# design.net
KiCad netlist of a schematic drawn in Altium Designer
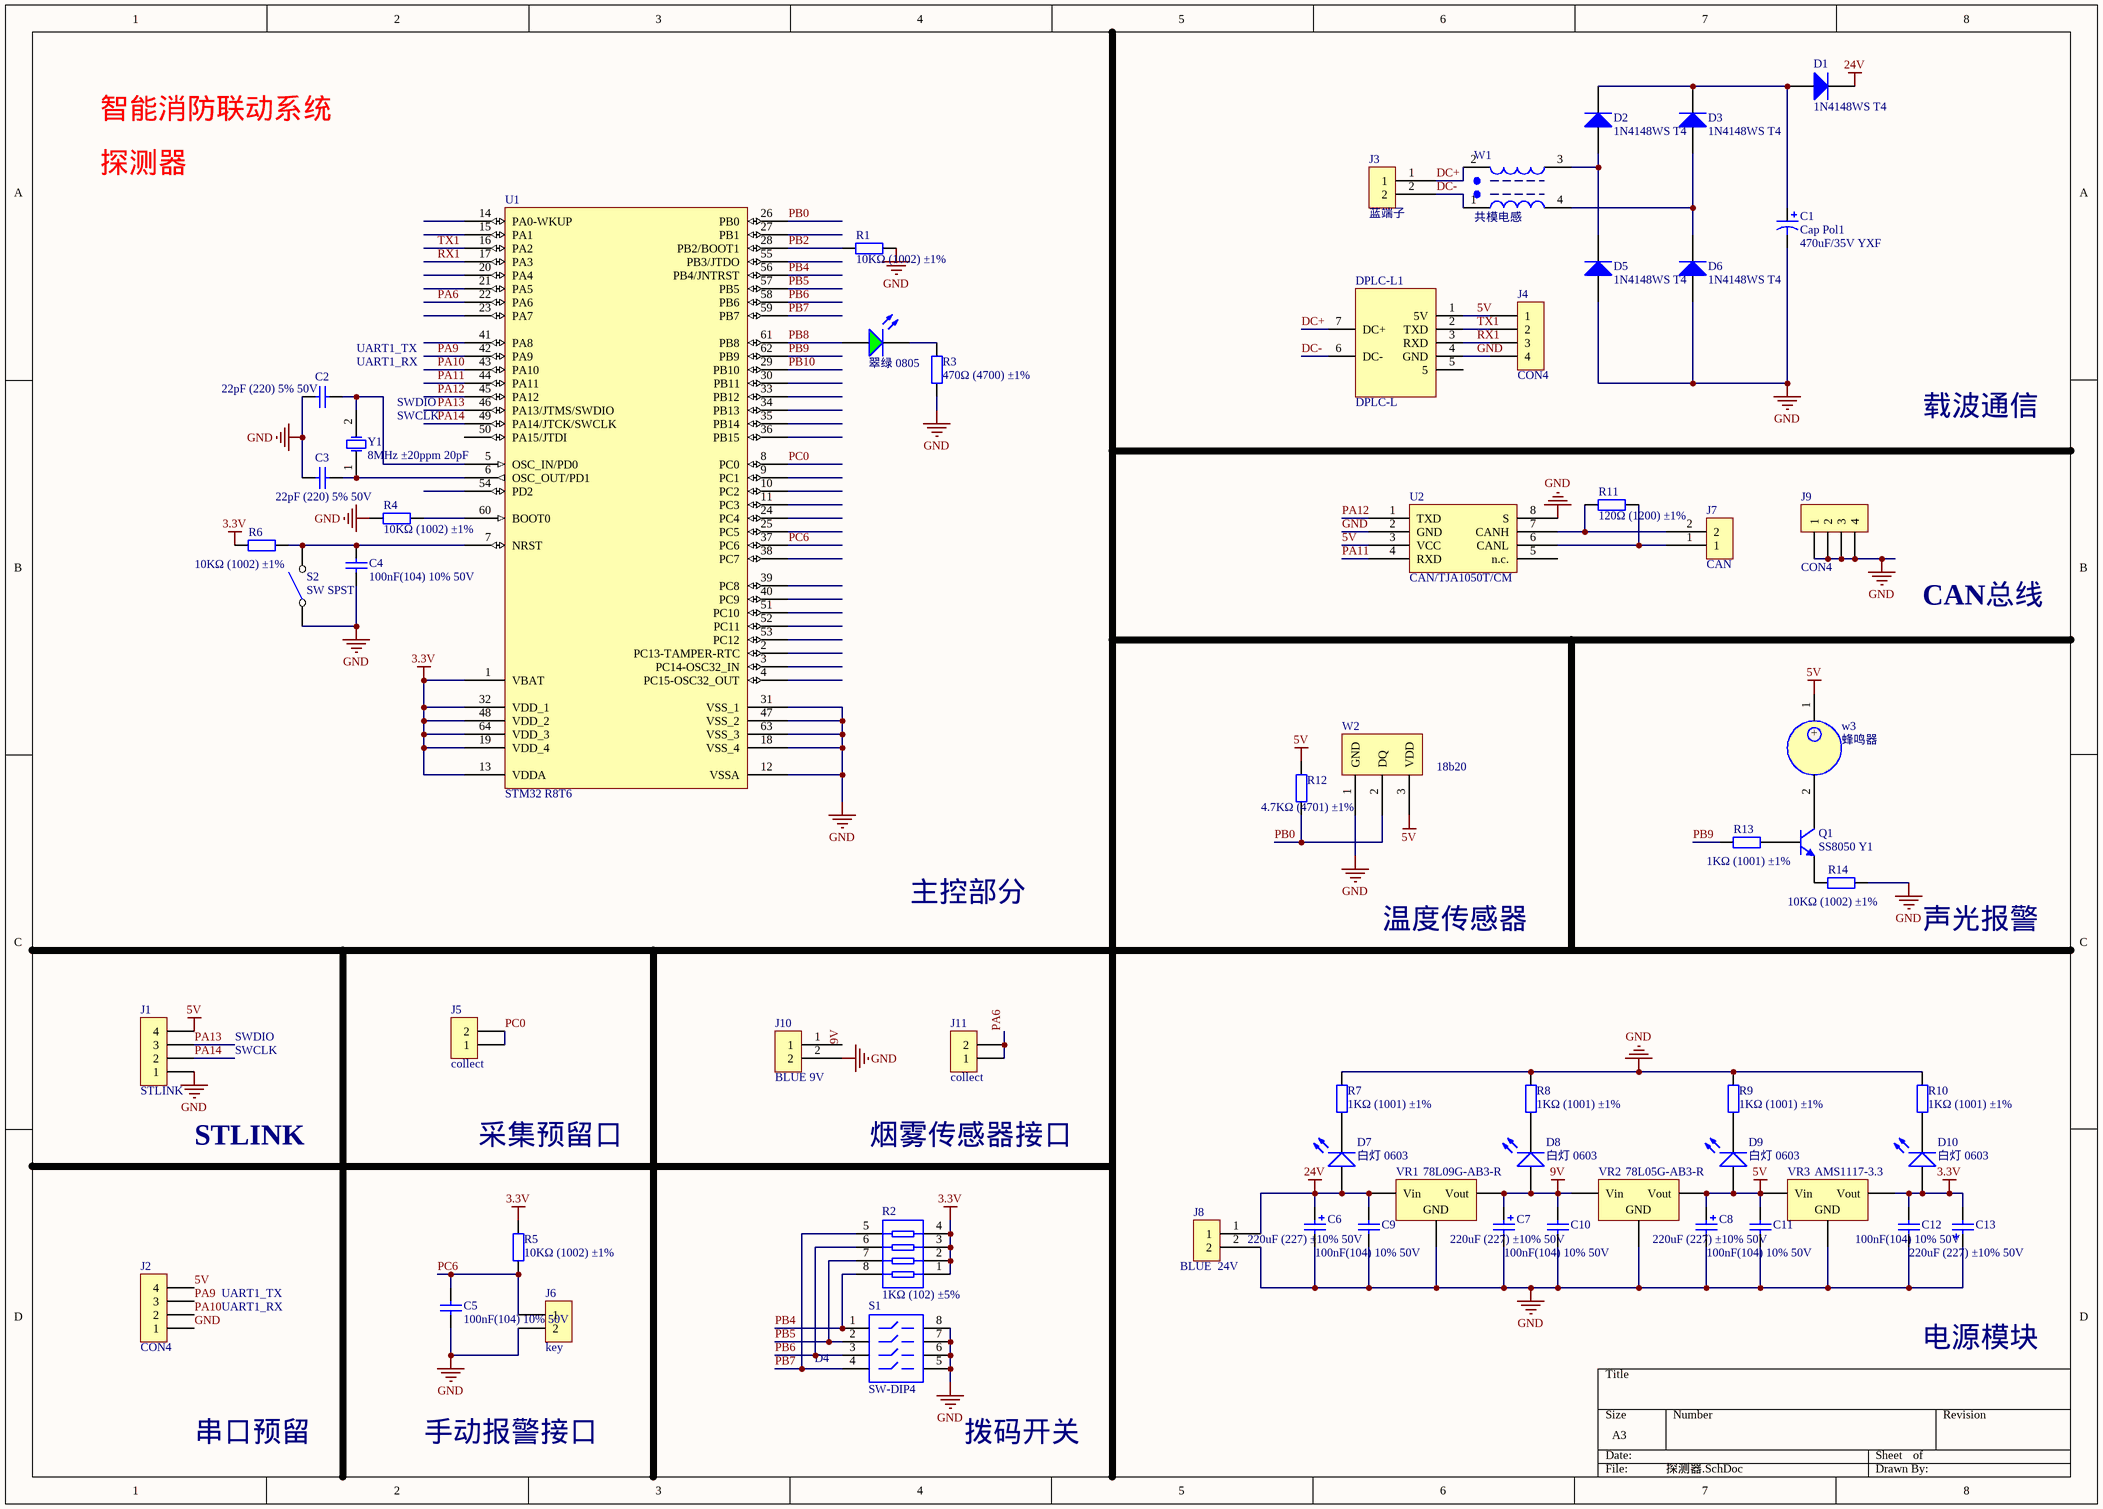
[diagram p0: 探测器.SchDoc]

(export (version "E")
  (design (tool "Eeschema 10.0.6"))
  (components
    (comp (ref "C1")
      (value "Cap Pol1")
      (footprint "RB.2/.4")
      (description "Polarized Capacitor (Radial)")
      (fields (field (name "ALTIUM_VALUE") "470uF/35V YXF") (field (name "PUBLISHER") "Altium Limited"))
      (libsource (lib "Miscellaneous Devices") (part "Cap Pol1"))
    )
    (comp (ref "C2")
      (value "22pF (220) 5% 50V")
      (footprint "LC-0805_C")
      (description "贴片电容")
      (libsource (lib "Miscellaneous Devices LC") (part "0805 22pF (220) 5% 50V"))
    )
    (comp (ref "C3")
      (value "22pF (220) 5% 50V")
      (footprint "LC-0805_C")
      (description "贴片电容")
      (libsource (lib "Miscellaneous Devices LC") (part "0805 22pF (220) 5% 50V"))
    )
    (comp (ref "C4")
      (value "100nF(104) 10% 50V")
      (footprint "LC-0805_C")
      (description "贴片电容")
      (libsource (lib "Miscellaneous Devices LC") (part "0805 100nF(104) 10% 50V"))
    )
    (comp (ref "C5")
      (value "100nF(104) 10% 50V")
      (footprint "LC-0805_C")
      (description "贴片电容")
      (libsource (lib "Miscellaneous Devices LC") (part "0805 100nF(104) 10% 50V"))
    )
    (comp (ref "C6")
      (value "220uF (227) ±10% 50V")
      (footprint "LC-CASE-B_3528")
      (description "钽电容")
      (libsource (lib "Miscellaneous Devices LC") (part "3528 100uF (107) 10% 6.3V"))
    )
    (comp (ref "C7")
      (value "220uF (227) ±10% 50V")
      (footprint "LC-CASE-B_3528")
      (description "钽电容")
      (libsource (lib "Miscellaneous Devices LC") (part "3528 100uF (107) 10% 6.3V"))
    )
    (comp (ref "C8")
      (value "220uF (227) ±10% 50V")
      (footprint "LC-CASE-B_3528")
      (description "钽电容")
      (libsource (lib "Miscellaneous Devices LC") (part "3528 100uF (107) 10% 6.3V"))
    )
    (comp (ref "C9")
      (value "100nF(104) 10% 50V")
      (footprint "LC-0805_C")
      (description "贴片电容")
      (libsource (lib "Miscellaneous Devices LC") (part "0805 100nF(104) 10% 50V"))
    )
    (comp (ref "C10")
      (value "100nF(104) 10% 50V")
      (footprint "LC-0805_C")
      (description "贴片电容")
      (libsource (lib "Miscellaneous Devices LC") (part "0805 100nF(104) 10% 50V"))
    )
    (comp (ref "C11")
      (value "100nF(104) 10% 50V")
      (footprint "LC-0805_C")
      (description "贴片电容")
      (libsource (lib "Miscellaneous Devices LC") (part "0805 100nF(104) 10% 50V"))
    )
    (comp (ref "C12")
      (value "100nF(104) 10% 50V")
      (footprint "LC-0805_C")
      (description "贴片电容")
      (libsource (lib "Miscellaneous Devices LC") (part "0805 100nF(104) 10% 50V"))
    )
    (comp (ref "C13")
      (value "220uF (227) ±10% 50V")
      (footprint "LC-CASE-B_3528")
      (description "钽电容")
      (libsource (lib "Miscellaneous Devices LC") (part "3528 100uF (107) 10% 6.3V"))
    )
    (comp (ref "D1")
      (value "1N4148WS T4")
      (footprint "LC-SOD-323")
      (description "二极管")
      (libsource (lib "Miscellaneous Devices LC") (part "SOD-323 1N4148WS T4"))
    )
    (comp (ref "D2")
      (value "1N4148WS T4")
      (footprint "LC-SOD-323")
      (description "二极管")
      (libsource (lib "Miscellaneous Devices LC") (part "SOD-323 1N4148WS T4"))
    )
    (comp (ref "D3")
      (value "1N4148WS T4")
      (footprint "LC-SOD-323")
      (description "二极管")
      (libsource (lib "Miscellaneous Devices LC") (part "SOD-323 1N4148WS T4"))
    )
    (comp (ref "D4")
      (value "翠绿 0805")
      (footprint "LC-0805_LED_S1")
      (description "发光二极管")
      (libsource (lib "Miscellaneous Devices LC") (part "0805 翠绿"))
    )
    (comp (ref "D5")
      (value "1N4148WS T4")
      (footprint "LC-SOD-323")
      (description "二极管")
      (libsource (lib "Miscellaneous Devices LC") (part "SOD-323 1N4148WS T4"))
    )
    (comp (ref "D6")
      (value "1N4148WS T4")
      (footprint "LC-SOD-323")
      (description "二极管")
      (libsource (lib "Miscellaneous Devices LC") (part "SOD-323 1N4148WS T4"))
    )
    (comp (ref "D7")
      (value "白灯 0603")
      (footprint "LC-0603_LED_S1")
      (description "发光二极管")
      (libsource (lib "Miscellaneous Devices LC") (part "0603 白灯"))
    )
    (comp (ref "D8")
      (value "白灯 0603")
      (footprint "LC-0603_LED_S1")
      (description "发光二极管")
      (libsource (lib "Miscellaneous Devices LC") (part "0603 白灯"))
    )
    (comp (ref "D9")
      (value "白灯 0603")
      (footprint "LC-0603_LED_S1")
      (description "发光二极管")
      (libsource (lib "Miscellaneous Devices LC") (part "0603 白灯"))
    )
    (comp (ref "D10")
      (value "白灯 0603")
      (footprint "LC-0603_LED_S1")
      (description "发光二极管")
      (libsource (lib "Miscellaneous Devices LC") (part "0603 白灯"))
    )
    (comp (ref "DPLC-L1") (value "DPLC-L") (footprint "DPLC-L") (libsource (lib "毕设原理图封装库") (part "DPLC-L")))
    (comp (ref "J1") (value "STLINK") (footprint "SIP4") (libsource (lib "") (part "CON4_1")))
    (comp (ref "J2") (value "CON4") (footprint "SIP4") (libsource (lib "") (part "CON4_1")))
    (comp (ref "J3") (value "蓝端子") (footprint "蓝端子") (libsource (lib "毕设原理图封装库") (part "蓝端子")))
    (comp (ref "J4") (value "CON4") (footprint "SIP4") (libsource (lib "") (part "CON4_2")))
    (comp (ref "J5") (value "collect") (footprint "SIP2") (libsource (lib "") (part "CON2_1")))
    (comp (ref "J6") (value "key") (footprint "SIP2") (libsource (lib "毕设原理图封装库") (part "CON2")))
    (comp (ref "J7") (value "CAN") (footprint "蓝端子") (libsource (lib "") (part "蓝端子_1")))
    (comp (ref "J8") (value "BLUE  24V") (footprint "蓝端子") (libsource (lib "毕设原理图封装库") (part "蓝端子")))
    (comp (ref "J9") (value "CON4") (footprint "SIP4") (libsource (lib "毕设原理图封装库") (part "CON4")))
    (comp (ref "J10") (value "BLUE 9V") (footprint "蓝端子") (libsource (lib "毕设原理图封装库") (part "蓝端子")))
    (comp (ref "J11") (value "collect") (footprint "SIP2") (libsource (lib "") (part "CON2_1")))
    (comp (ref "Q1")
      (value "SS8050 Y1")
      (footprint "LC-SOT-23(SOT-23-3)")
      (description "三极管")
      (libsource (lib "Miscellaneous Devices LC") (part "SOT-23 SS8050 Y1"))
    )
    (comp (ref "R1")
      (value "10KΩ (1002) ±1%")
      (footprint "LC-0805_R")
      (description "贴片电阻")
      (libsource (lib "Miscellaneous Devices LC") (part "0805 10KΩ (1002) 1%"))
    )
    (comp (ref "R2")
      (value "1KΩ (102) ±5%")
      (footprint "LC-0603_Rx4")
      (description "贴片排阻")
      (libsource (lib "Miscellaneous Devices LC") (part "0603*4  1KΩ (102) 5%"))
    )
    (comp (ref "R3")
      (value "470Ω (4700) ±1%")
      (footprint "LC-0805_R")
      (description "贴片电阻")
      (libsource (lib "Miscellaneous Devices LC") (part "0805 470Ω (4700) 1%"))
    )
    (comp (ref "R4")
      (value "10KΩ (1002) ±1%")
      (footprint "LC-0805_R")
      (description "贴片电阻")
      (libsource (lib "") (part "0805 10KΩ (1002) 1%_1"))
    )
    (comp (ref "R5")
      (value "10KΩ (1002) ±1%")
      (footprint "LC-0805_R")
      (description "贴片电阻")
      (libsource (lib "") (part "0805 10KΩ (1002) 1%_2"))
    )
    (comp (ref "R6")
      (value "10KΩ (1002) ±1%")
      (footprint "LC-0805_R")
      (description "贴片电阻")
      (libsource (lib "") (part "0805 10KΩ (1002) 1%_1"))
    )
    (comp (ref "R7")
      (value "1KΩ (1001) ±1%")
      (footprint "LC-0603_R")
      (description "贴片电阻")
      (libsource (lib "Miscellaneous Devices LC") (part "0603 1KΩ (1001) 1%"))
    )
    (comp (ref "R8")
      (value "1KΩ (1001) ±1%")
      (footprint "LC-0603_R")
      (description "贴片电阻")
      (libsource (lib "Miscellaneous Devices LC") (part "0603 1KΩ (1001) 1%"))
    )
    (comp (ref "R9")
      (value "1KΩ (1001) ±1%")
      (footprint "LC-0603_R")
      (description "贴片电阻")
      (libsource (lib "Miscellaneous Devices LC") (part "0603 1KΩ (1001) 1%"))
    )
    (comp (ref "R10")
      (value "1KΩ (1001) ±1%")
      (footprint "LC-0603_R")
      (description "贴片电阻")
      (libsource (lib "Miscellaneous Devices LC") (part "0603 1KΩ (1001) 1%"))
    )
    (comp (ref "R11")
      (value "120Ω (1200) ±1%")
      (footprint "LC-0805_R")
      (description "贴片电阻")
      (libsource (lib "Miscellaneous Devices LC") (part "0805 120Ω (1200) 1%"))
    )
    (comp (ref "R12")
      (value "4.7KΩ (4701) ±1%")
      (footprint "LC-0805_R")
      (description "贴片电阻")
      (libsource (lib "Miscellaneous Devices LC") (part "0805 4.7KΩ (4701) 1%"))
    )
    (comp (ref "R13")
      (value "1KΩ (1001) ±1%")
      (footprint "LC-0805_R")
      (description "贴片电阻")
      (libsource (lib "Miscellaneous Devices LC") (part "0805 1KΩ (1001) 1%"))
    )
    (comp (ref "R14")
      (value "10KΩ (1002) ±1%")
      (footprint "LC-0805_R")
      (description "贴片电阻")
      (libsource (lib "") (part "0805 10KΩ (1002) 1%_1"))
    )
    (comp (ref "S1")
      (value "SW-DIP4")
      (footprint "4位拨码开关")
      (description "4位拨码开关")
      (libsource (lib "毕设原理图封装库") (part "SW-DIP4"))
    )
    (comp (ref "S2")
      (value "SW SPST")
      (footprint "单片机小按键")
      (description "单刀单掷开关")
      (libsource (lib "毕设原理图封装库") (part "SW SPST"))
    )
    (comp (ref "U1")
      (value "STM32 R8T6")
      (footprint "LC-LQFP-64_10x10x05P")
      (libsource (lib "毕设原理图封装库") (part "STM32 R8T6"))
    )
    (comp (ref "U2")
      (value "CAN/TJA1050T/CM")
      (footprint "LC-SOIC-8_150mil")
      (description "CAN")
      (libsource (lib "Miscellaneous Devices LC") (part "CAN/TJA1050T/CM"))
    )
    (comp (ref "VR1")
      (value "78L09G-AB3-R")
      (footprint "LC-SOT-89(SOT-89-3)")
      (description "低压差线性稳压(LDO)")
      (libsource (lib "Miscellaneous Devices LC") (part "SOT-89 78L12G-AB3-R"))
    )
    (comp (ref "VR2")
      (value "78L05G-AB3-R")
      (footprint "LC-SOT-89(SOT-89-3)")
      (description "低压差线性稳压(LDO)")
      (libsource (lib "Miscellaneous Devices LC") (part "SOT-89 78L05G-AB3-R"))
    )
    (comp (ref "VR3")
      (value "AMS1117-3.3")
      (footprint "LC-SOT-223")
      (description "低压差线性稳压(LDO)")
      (libsource (lib "Miscellaneous Devices LC") (part "SOT-223 AMS1117-3.3"))
    )
    (comp (ref "W1") (value "共模电感") (footprint "共模电感") (libsource (lib "毕设原理图封装库") (part "共模电感")))
    (comp (ref "W2") (value "18b20") (footprint "DS18B20") (libsource (lib "毕设原理图封装库") (part "18b20")))
    (comp (ref "w3") (value "蜂鸣器") (footprint "蜂鸣器") (libsource (lib "毕设原理图封装库") (part "蜂鸣器")))
    (comp (ref "Y1")
      (value "8MHz ±20ppm 20pF")
      (footprint "LC-SMD-5032_2P")
      (description "贴片晶振")
      (libsource (lib "Miscellaneous Devices LC") (part "SMD-5032_2P 8MHz 20ppm 20pF"))
    )
  )
  (nets
    (net (code "1") (name "/DC+") (class "Default")
      (node (ref "DPLC-L1") (pin "7") (pinfunction "DC+_7") (pintype "passive"))
      (node (ref "J3") (pin "1") (pinfunction "1_1") (pintype "passive"))
      (node (ref "W1") (pin "2") (pinfunction "2_2") (pintype "passive"))
    )
    (net (code "2") (name "/DC-") (class "Default")
      (node (ref "DPLC-L1") (pin "6") (pinfunction "DC-_6") (pintype "passive"))
      (node (ref "J3") (pin "2") (pinfunction "2_2") (pintype "passive"))
      (node (ref "W1") (pin "1") (pinfunction "1_1") (pintype "passive"))
    )
    (net (code "3") (name "/PA6") (class "Default")
      (node (ref "J11") (pin "1") (pinfunction "1_1") (pintype "passive"))
      (node (ref "J11") (pin "2") (pinfunction "2_2") (pintype "passive"))
      (node (ref "U1") (pin "22") (pinfunction "PA6_22") (pintype "bidirectional"))
    )
    (net (code "4") (name "/PA9") (class "Default")
      (node (ref "J2") (pin "3") (pinfunction "3_3") (pintype "passive"))
      (node (ref "U1") (pin "42") (pinfunction "PA9_42") (pintype "bidirectional"))
    )
    (net (code "5") (name "/PA10") (class "Default")
      (node (ref "J2") (pin "2") (pinfunction "2_2") (pintype "passive"))
      (node (ref "U1") (pin "43") (pinfunction "PA10_43") (pintype "bidirectional"))
    )
    (net (code "6") (name "/PA11") (class "Default")
      (node (ref "U1") (pin "44") (pinfunction "PA11_44") (pintype "bidirectional"))
      (node (ref "U2") (pin "4") (pinfunction "RXD_4") (pintype "passive"))
    )
    (net (code "7") (name "/PA12") (class "Default")
      (node (ref "U1") (pin "45") (pinfunction "PA12_45") (pintype "bidirectional"))
      (node (ref "U2") (pin "1") (pinfunction "TXD_1") (pintype "passive"))
    )
    (net (code "8") (name "/PA13") (class "Default")
      (node (ref "J1") (pin "3") (pinfunction "3_3") (pintype "passive"))
      (node (ref "U1") (pin "46") (pinfunction "PA13/JTMS/SWDIO_46") (pintype "bidirectional"))
    )
    (net (code "9") (name "/PA14") (class "Default")
      (node (ref "J1") (pin "2") (pinfunction "2_2") (pintype "passive"))
      (node (ref "U1") (pin "49") (pinfunction "PA14/JTCK/SWCLK_49") (pintype "bidirectional"))
    )
    (net (code "10") (name "/PB0") (class "Default")
      (node (ref "R12") (pin "1") (pinfunction "1_1") (pintype "passive"))
      (node (ref "U1") (pin "26") (pinfunction "PB0_26") (pintype "bidirectional"))
      (node (ref "W2") (pin "2") (pinfunction "DQ_2") (pintype "passive"))
    )
    (net (code "11") (name "/PB2") (class "Default")
      (node (ref "R1") (pin "2") (pinfunction "2_2") (pintype "passive"))
      (node (ref "U1") (pin "28") (pinfunction "PB2/BOOT1_28") (pintype "bidirectional"))
    )
    (net (code "12") (name "/PB4") (class "Default")
      (node (ref "R2") (pin "8") (pinfunction "8_8") (pintype "passive"))
      (node (ref "S1") (pin "1") (pinfunction "1_1") (pintype "passive"))
      (node (ref "U1") (pin "56") (pinfunction "PB4/JNTRST_56") (pintype "bidirectional"))
    )
    (net (code "13") (name "/PB5") (class "Default")
      (node (ref "R2") (pin "7") (pinfunction "7_7") (pintype "passive"))
      (node (ref "S1") (pin "2") (pinfunction "2_2") (pintype "passive"))
      (node (ref "U1") (pin "57") (pinfunction "PB5_57") (pintype "bidirectional"))
    )
    (net (code "14") (name "/PB6") (class "Default")
      (node (ref "R2") (pin "6") (pinfunction "6_6") (pintype "passive"))
      (node (ref "S1") (pin "3") (pinfunction "3_3") (pintype "passive"))
      (node (ref "U1") (pin "58") (pinfunction "PB6_58") (pintype "bidirectional"))
    )
    (net (code "15") (name "/PB7") (class "Default")
      (node (ref "R2") (pin "5") (pinfunction "5_5") (pintype "passive"))
      (node (ref "S1") (pin "4") (pinfunction "4_4") (pintype "passive"))
      (node (ref "U1") (pin "59") (pinfunction "PB7_59") (pintype "bidirectional"))
    )
    (net (code "16") (name "/PB8") (class "Default")
      (node (ref "D4") (pin "A") (pinfunction "A_A") (pintype "passive"))
      (node (ref "U1") (pin "61") (pinfunction "PB8_61") (pintype "bidirectional"))
    )
    (net (code "17") (name "/PB9") (class "Default")
      (node (ref "R13") (pin "1") (pinfunction "1_1") (pintype "passive"))
      (node (ref "U1") (pin "62") (pinfunction "PB9_62") (pintype "bidirectional"))
    )
    (net (code "18") (name "/PB10") (class "Default")
      (node (ref "U1") (pin "29") (pinfunction "PB10_29") (pintype "bidirectional"))
    )
    (net (code "19") (name "/PC0") (class "Default")
      (node (ref "J5") (pin "1") (pinfunction "1_1") (pintype "passive"))
      (node (ref "J5") (pin "2") (pinfunction "2_2") (pintype "passive"))
      (node (ref "U1") (pin "8") (pinfunction "PC0_8") (pintype "bidirectional"))
    )
    (net (code "20") (name "/PC6") (class "Default")
      (node (ref "C5") (pin "2") (pinfunction "2_2") (pintype "passive"))
      (node (ref "J6") (pin "1") (pinfunction "1_1") (pintype "passive"))
      (node (ref "R5") (pin "1") (pinfunction "1_1") (pintype "passive"))
      (node (ref "U1") (pin "37") (pinfunction "PC6_37") (pintype "bidirectional"))
    )
    (net (code "21") (name "/RX1") (class "Default")
      (node (ref "DPLC-L1") (pin "3") (pinfunction "RXD_3") (pintype "passive"))
      (node (ref "J4") (pin "3") (pinfunction "3_3") (pintype "passive"))
      (node (ref "U1") (pin "17") (pinfunction "PA3_17") (pintype "bidirectional"))
    )
    (net (code "22") (name "/TX1") (class "Default")
      (node (ref "DPLC-L1") (pin "2") (pinfunction "TXD_2") (pintype "passive"))
      (node (ref "J4") (pin "2") (pinfunction "2_2") (pintype "passive"))
      (node (ref "U1") (pin "16") (pinfunction "PA2_16") (pintype "bidirectional"))
    )
    (net (code "23") (name "3.3V") (class "Default")
      (node (ref "C12") (pin "1") (pinfunction "1_1") (pintype "passive"))
      (node (ref "C13") (pin "2") (pinfunction "2_2") (pintype "passive"))
      (node (ref "D10") (pin "A") (pinfunction "A_A") (pintype "passive"))
      (node (ref "R2") (pin "1") (pinfunction "1_1") (pintype "passive"))
      (node (ref "R2") (pin "2") (pinfunction "2_2") (pintype "passive"))
      (node (ref "R2") (pin "3") (pinfunction "3_3") (pintype "passive"))
      (node (ref "R2") (pin "4") (pinfunction "4_4") (pintype "passive"))
      (node (ref "R5") (pin "2") (pinfunction "2_2") (pintype "passive"))
      (node (ref "R6") (pin "1") (pinfunction "1_1") (pintype "passive"))
      (node (ref "U1") (pin "1") (pinfunction "VBAT_1") (pintype "power_in"))
      (node (ref "U1") (pin "13") (pinfunction "VDDA_13") (pintype "power_in"))
      (node (ref "U1") (pin "19") (pinfunction "VDD_4_19") (pintype "power_in"))
      (node (ref "U1") (pin "32") (pinfunction "VDD_1_32") (pintype "power_in"))
      (node (ref "U1") (pin "48") (pinfunction "VDD_2_48") (pintype "power_in"))
      (node (ref "U1") (pin "64") (pinfunction "VDD_3_64") (pintype "power_in"))
      (node (ref "VR3") (pin "2") (pinfunction "Vout_2") (pintype "passive"))
    )
    (net (code "24") (name "5V") (class "Default")
      (node (ref "C11") (pin "2") (pinfunction "2_2") (pintype "passive"))
      (node (ref "C8") (pin "1") (pinfunction "1_1") (pintype "passive"))
      (node (ref "D9") (pin "A") (pinfunction "A_A") (pintype "passive"))
      (node (ref "DPLC-L1") (pin "1") (pinfunction "5V_1") (pintype "passive"))
      (node (ref "J1") (pin "4") (pinfunction "4_4") (pintype "passive"))
      (node (ref "J2") (pin "4") (pinfunction "4_4") (pintype "passive"))
      (node (ref "J4") (pin "1") (pinfunction "1_1") (pintype "passive"))
      (node (ref "R12") (pin "2") (pinfunction "2_2") (pintype "passive"))
      (node (ref "U2") (pin "3") (pinfunction "VCC_3") (pintype "passive"))
      (node (ref "VR2") (pin "3") (pinfunction "Vout_3") (pintype "passive"))
      (node (ref "VR3") (pin "3") (pinfunction "Vin_3") (pintype "passive"))
      (node (ref "W2") (pin "3") (pinfunction "VDD_3") (pintype "passive"))
      (node (ref "w3") (pin "1") (pinfunction "+_1") (pintype "passive"))
    )
    (net (code "25") (name "9V") (class "Default")
      (node (ref "C10") (pin "2") (pinfunction "2_2") (pintype "passive"))
      (node (ref "C7") (pin "1") (pinfunction "1_1") (pintype "passive"))
      (node (ref "D8") (pin "A") (pinfunction "A_A") (pintype "passive"))
      (node (ref "J10") (pin "1") (pinfunction "1_1") (pintype "passive"))
      (node (ref "VR1") (pin "3") (pinfunction "Vout_3") (pintype "passive"))
      (node (ref "VR2") (pin "1") (pinfunction "Vin_1") (pintype "passive"))
    )
    (net (code "26") (name "24V") (class "Default")
      (node (ref "C6") (pin "1") (pinfunction "1_1") (pintype "passive"))
      (node (ref "C9") (pin "2") (pinfunction "2_2") (pintype "passive"))
      (node (ref "D1") (pin "2") (pinfunction "K_2") (pintype "passive"))
      (node (ref "D7") (pin "A") (pinfunction "A_A") (pintype "passive"))
      (node (ref "J8") (pin "1") (pinfunction "1_1") (pintype "passive"))
      (node (ref "VR1") (pin "1") (pinfunction "Vin_1") (pintype "passive"))
    )
    (net (code "27") (name "GND") (class "Default")
      (node (ref "C1") (pin "2") (pinfunction "2_2") (pintype "passive"))
      (node (ref "C10") (pin "1") (pinfunction "1_1") (pintype "passive"))
      (node (ref "C11") (pin "1") (pinfunction "1_1") (pintype "passive"))
      (node (ref "C12") (pin "2") (pinfunction "2_2") (pintype "passive"))
      (node (ref "C13") (pin "1") (pinfunction "1_1") (pintype "passive"))
      (node (ref "C2") (pin "1") (pinfunction "1_1") (pintype "passive"))
      (node (ref "C3") (pin "1") (pinfunction "1_1") (pintype "passive"))
      (node (ref "C4") (pin "1") (pinfunction "1_1") (pintype "passive"))
      (node (ref "C5") (pin "1") (pinfunction "1_1") (pintype "passive"))
      (node (ref "C6") (pin "2") (pinfunction "2_2") (pintype "passive"))
      (node (ref "C7") (pin "2") (pinfunction "2_2") (pintype "passive"))
      (node (ref "C8") (pin "2") (pinfunction "2_2") (pintype "passive"))
      (node (ref "C9") (pin "1") (pinfunction "1_1") (pintype "passive"))
      (node (ref "D5") (pin "1") (pinfunction "A_1") (pintype "passive"))
      (node (ref "D6") (pin "1") (pinfunction "A_1") (pintype "passive"))
      (node (ref "DPLC-L1") (pin "4") (pinfunction "GND_4") (pintype "passive"))
      (node (ref "J1") (pin "1") (pinfunction "1_1") (pintype "passive"))
      (node (ref "J10") (pin "2") (pinfunction "2_2") (pintype "passive"))
      (node (ref "J2") (pin "1") (pinfunction "1_1") (pintype "passive"))
      (node (ref "J4") (pin "4") (pinfunction "4_4") (pintype "passive"))
      (node (ref "J6") (pin "2") (pinfunction "2_2") (pintype "passive"))
      (node (ref "J8") (pin "2") (pinfunction "2_2") (pintype "passive"))
      (node (ref "J9") (pin "1") (pinfunction "1_1") (pintype "passive"))
      (node (ref "J9") (pin "2") (pinfunction "2_2") (pintype "passive"))
      (node (ref "J9") (pin "3") (pinfunction "3_3") (pintype "passive"))
      (node (ref "J9") (pin "4") (pinfunction "4_4") (pintype "passive"))
      (node (ref "R1") (pin "1") (pinfunction "1_1") (pintype "passive"))
      (node (ref "R10") (pin "1") (pinfunction "1_1") (pintype "passive"))
      (node (ref "R14") (pin "2") (pinfunction "2_2") (pintype "passive"))
      (node (ref "R3") (pin "1") (pinfunction "1_1") (pintype "passive"))
      (node (ref "R4") (pin "1") (pinfunction "1_1") (pintype "passive"))
      (node (ref "R7") (pin "1") (pinfunction "1_1") (pintype "passive"))
      (node (ref "R8") (pin "1") (pinfunction "1_1") (pintype "passive"))
      (node (ref "R9") (pin "1") (pinfunction "1_1") (pintype "passive"))
      (node (ref "S1") (pin "5") (pinfunction "5_5") (pintype "passive"))
      (node (ref "S1") (pin "6") (pinfunction "6_6") (pintype "passive"))
      (node (ref "S1") (pin "7") (pinfunction "7_7") (pintype "passive"))
      (node (ref "S1") (pin "8") (pinfunction "8_8") (pintype "passive"))
      (node (ref "S2") (pin "1") (pinfunction "COMMON_1") (pintype "passive"))
      (node (ref "U1") (pin "12") (pinfunction "VSSA_12") (pintype "power_in"))
      (node (ref "U1") (pin "18") (pinfunction "VSS_4_18") (pintype "power_in"))
      (node (ref "U1") (pin "31") (pinfunction "VSS_1_31") (pintype "power_in"))
      (node (ref "U1") (pin "47") (pinfunction "VSS_2_47") (pintype "power_in"))
      (node (ref "U1") (pin "63") (pinfunction "VSS_3_63") (pintype "power_in"))
      (node (ref "U2") (pin "2") (pinfunction "GND_2") (pintype "passive"))
      (node (ref "U2") (pin "8") (pinfunction "S_8") (pintype "passive"))
      (node (ref "VR1") (pin "2") (pinfunction "GND_2") (pintype "passive"))
      (node (ref "VR2") (pin "2") (pinfunction "GND_2") (pintype "passive"))
      (node (ref "VR3") (pin "1") (pinfunction "GND_1") (pintype "passive"))
      (node (ref "W2") (pin "1") (pinfunction "GND_1") (pintype "passive"))
    )
    (net (code "28") (name "Net-(D1-A)") (class "Default")
      (node (ref "C1") (pin "1") (pinfunction "1_1") (pintype "passive"))
      (node (ref "D1") (pin "1") (pinfunction "A_1") (pintype "passive"))
      (node (ref "D2") (pin "2") (pinfunction "K_2") (pintype "passive"))
      (node (ref "D3") (pin "2") (pinfunction "K_2") (pintype "passive"))
    )
    (net (code "29") (name "Net-(D2-A)") (class "Default")
      (node (ref "D2") (pin "1") (pinfunction "A_1") (pintype "passive"))
      (node (ref "D5") (pin "2") (pinfunction "K_2") (pintype "passive"))
      (node (ref "W1") (pin "3") (pinfunction "3_3") (pintype "passive"))
    )
    (net (code "30") (name "Net-(D3-A)") (class "Default")
      (node (ref "D3") (pin "1") (pinfunction "A_1") (pintype "passive"))
      (node (ref "D6") (pin "2") (pinfunction "K_2") (pintype "passive"))
      (node (ref "W1") (pin "4") (pinfunction "4_4") (pintype "passive"))
    )
    (net (code "31") (name "Net-(D4-PadK)") (class "Default")
      (node (ref "D4") (pin "K") (pinfunction "K_K") (pintype "passive"))
      (node (ref "R3") (pin "2") (pinfunction "2_2") (pintype "passive"))
    )
    (net (code "32") (name "Net-(D7-PadK)") (class "Default")
      (node (ref "D7") (pin "K") (pinfunction "K_K") (pintype "passive"))
      (node (ref "R7") (pin "2") (pinfunction "2_2") (pintype "passive"))
    )
    (net (code "33") (name "Net-(D8-PadK)") (class "Default")
      (node (ref "D8") (pin "K") (pinfunction "K_K") (pintype "passive"))
      (node (ref "R8") (pin "2") (pinfunction "2_2") (pintype "passive"))
    )
    (net (code "34") (name "Net-(D9-PadK)") (class "Default")
      (node (ref "D9") (pin "K") (pinfunction "K_K") (pintype "passive"))
      (node (ref "R9") (pin "2") (pinfunction "2_2") (pintype "passive"))
    )
    (net (code "35") (name "Net-(D10-PadK)") (class "Default")
      (node (ref "D10") (pin "K") (pinfunction "K_K") (pintype "passive"))
      (node (ref "R10") (pin "2") (pinfunction "2_2") (pintype "passive"))
    )
    (net (code "36") (name "Net-(Q1-B)") (class "Default")
      (node (ref "Q1") (pin "1") (pinfunction "B_1") (pintype "passive"))
      (node (ref "R13") (pin "2") (pinfunction "2_2") (pintype "passive"))
    )
    (net (code "37") (name "Net-(Q1-C)") (class "Default")
      (node (ref "Q1") (pin "3") (pinfunction "C_3") (pintype "passive"))
      (node (ref "w3") (pin "2") (pintype "passive"))
    )
    (net (code "38") (name "Net-(Q1-E)") (class "Default")
      (node (ref "Q1") (pin "2") (pinfunction "E_2") (pintype "passive"))
      (node (ref "R14") (pin "1") (pinfunction "1_1") (pintype "passive"))
    )
    (net (code "39") (name "Net-(S2-NO)") (class "Default")
      (node (ref "C4") (pin "2") (pinfunction "2_2") (pintype "passive"))
      (node (ref "R6") (pin "2") (pinfunction "2_2") (pintype "passive"))
      (node (ref "S2") (pin "2") (pinfunction "NO_2") (pintype "passive"))
      (node (ref "U1") (pin "7") (pinfunction "NRST_7") (pintype "bidirectional"))
    )
    (net (code "40") (name "Net-(U1-BOOT0)") (class "Default")
      (node (ref "R4") (pin "2") (pinfunction "2_2") (pintype "passive"))
      (node (ref "U1") (pin "60") (pinfunction "BOOT0_60") (pintype "input"))
    )
    (net (code "41") (name "Net-(U1-OSC_IN{slash}PD0)") (class "Default")
      (node (ref "C2") (pin "2") (pinfunction "2_2") (pintype "passive"))
      (node (ref "U1") (pin "5") (pinfunction "OSC_IN/PD0_5") (pintype "input"))
      (node (ref "Y1") (pin "2") (pinfunction "OSC2_2") (pintype "passive"))
    )
    (net (code "42") (name "Net-(U1-OSC_OUT{slash}PD1)") (class "Default")
      (node (ref "C3") (pin "2") (pinfunction "2_2") (pintype "passive"))
      (node (ref "U1") (pin "6") (pinfunction "OSC_OUT/PD1_6") (pintype "output"))
      (node (ref "Y1") (pin "1") (pinfunction "OSC1_1") (pintype "passive"))
    )
    (net (code "43") (name "Net-(U2-CANH)") (class "Default")
      (node (ref "J7") (pin "2") (pinfunction "2_2") (pintype "passive"))
      (node (ref "R11") (pin "1") (pinfunction "1_1") (pintype "passive"))
      (node (ref "U2") (pin "7") (pinfunction "CANH_7") (pintype "passive"))
    )
    (net (code "44") (name "Net-(U2-CANL)") (class "Default")
      (node (ref "J7") (pin "1") (pinfunction "1_1") (pintype "passive"))
      (node (ref "R11") (pin "2") (pinfunction "2_2") (pintype "passive"))
      (node (ref "U2") (pin "6") (pinfunction "CANL_6") (pintype "passive"))
    )
    (net (code "45") (name "unconnected-(DPLC-L1-Pad5)") (class "Default")
      (node (ref "DPLC-L1") (pin "5") (pinfunction "5_5") (pintype "passive"))
    )
    (net (code "46") (name "unconnected-(U1-PA0-WKUP-Pad14)") (class "Default")
      (node (ref "U1") (pin "14") (pinfunction "PA0-WKUP_14") (pintype "bidirectional"))
    )
    (net (code "47") (name "unconnected-(U1-PA1-Pad15)") (class "Default")
      (node (ref "U1") (pin "15") (pinfunction "PA1_15") (pintype "bidirectional"))
    )
    (net (code "48") (name "unconnected-(U1-PA4-Pad20)") (class "Default")
      (node (ref "U1") (pin "20") (pinfunction "PA4_20") (pintype "bidirectional"))
    )
    (net (code "49") (name "unconnected-(U1-PA5-Pad21)") (class "Default")
      (node (ref "U1") (pin "21") (pinfunction "PA5_21") (pintype "bidirectional"))
    )
    (net (code "50") (name "unconnected-(U1-PA7-Pad23)") (class "Default")
      (node (ref "U1") (pin "23") (pinfunction "PA7_23") (pintype "bidirectional"))
    )
    (net (code "51") (name "unconnected-(U1-PA8-Pad41)") (class "Default")
      (node (ref "U1") (pin "41") (pinfunction "PA8_41") (pintype "bidirectional"))
    )
    (net (code "52") (name "unconnected-(U1-PA15{slash}JTDI-Pad50)") (class "Default")
      (node (ref "U1") (pin "50") (pinfunction "PA15/JTDI_50") (pintype "bidirectional"))
    )
    (net (code "53") (name "unconnected-(U1-PB1-Pad27)") (class "Default")
      (node (ref "U1") (pin "27") (pinfunction "PB1_27") (pintype "bidirectional"))
    )
    (net (code "54") (name "unconnected-(U1-PB3{slash}JTDO-Pad55)") (class "Default")
      (node (ref "U1") (pin "55") (pinfunction "PB3/JTDO_55") (pintype "bidirectional"))
    )
    (net (code "55") (name "unconnected-(U1-PB11-Pad30)") (class "Default")
      (node (ref "U1") (pin "30") (pinfunction "PB11_30") (pintype "bidirectional"))
    )
    (net (code "56") (name "unconnected-(U1-PB12-Pad33)") (class "Default")
      (node (ref "U1") (pin "33") (pinfunction "PB12_33") (pintype "bidirectional"))
    )
    (net (code "57") (name "unconnected-(U1-PB13-Pad34)") (class "Default")
      (node (ref "U1") (pin "34") (pinfunction "PB13_34") (pintype "bidirectional"))
    )
    (net (code "58") (name "unconnected-(U1-PB14-Pad35)") (class "Default")
      (node (ref "U1") (pin "35") (pinfunction "PB14_35") (pintype "bidirectional"))
    )
    (net (code "59") (name "unconnected-(U1-PB15-Pad36)") (class "Default")
      (node (ref "U1") (pin "36") (pinfunction "PB15_36") (pintype "bidirectional"))
    )
    (net (code "60") (name "unconnected-(U1-PC1-Pad9)") (class "Default")
      (node (ref "U1") (pin "9") (pinfunction "PC1_9") (pintype "bidirectional"))
    )
    (net (code "61") (name "unconnected-(U1-PC2-Pad10)") (class "Default")
      (node (ref "U1") (pin "10") (pinfunction "PC2_10") (pintype "bidirectional"))
    )
    (net (code "62") (name "unconnected-(U1-PC3-Pad11)") (class "Default")
      (node (ref "U1") (pin "11") (pinfunction "PC3_11") (pintype "bidirectional"))
    )
    (net (code "63") (name "unconnected-(U1-PC4-Pad24)") (class "Default")
      (node (ref "U1") (pin "24") (pinfunction "PC4_24") (pintype "bidirectional"))
    )
    (net (code "64") (name "unconnected-(U1-PC5-Pad25)") (class "Default")
      (node (ref "U1") (pin "25") (pinfunction "PC5_25") (pintype "bidirectional"))
    )
    (net (code "65") (name "unconnected-(U1-PC7-Pad38)") (class "Default")
      (node (ref "U1") (pin "38") (pinfunction "PC7_38") (pintype "bidirectional"))
    )
    (net (code "66") (name "unconnected-(U1-PC8-Pad39)") (class "Default")
      (node (ref "U1") (pin "39") (pinfunction "PC8_39") (pintype "bidirectional"))
    )
    (net (code "67") (name "unconnected-(U1-PC9-Pad40)") (class "Default")
      (node (ref "U1") (pin "40") (pinfunction "PC9_40") (pintype "bidirectional"))
    )
    (net (code "68") (name "unconnected-(U1-PC10-Pad51)") (class "Default")
      (node (ref "U1") (pin "51") (pinfunction "PC10_51") (pintype "bidirectional"))
    )
    (net (code "69") (name "unconnected-(U1-PC11-Pad52)") (class "Default")
      (node (ref "U1") (pin "52") (pinfunction "PC11_52") (pintype "bidirectional"))
    )
    (net (code "70") (name "unconnected-(U1-PC12-Pad53)") (class "Default")
      (node (ref "U1") (pin "53") (pinfunction "PC12_53") (pintype "bidirectional"))
    )
    (net (code "71") (name "unconnected-(U1-PC13-TAMPER-RTC-Pad2)") (class "Default")
      (node (ref "U1") (pin "2") (pinfunction "PC13-TAMPER-RTC_2") (pintype "bidirectional"))
    )
    (net (code "72") (name "unconnected-(U1-PC14-OSC32_IN-Pad3)") (class "Default")
      (node (ref "U1") (pin "3") (pinfunction "PC14-OSC32_IN_3") (pintype "bidirectional"))
    )
    (net (code "73") (name "unconnected-(U1-PC15-OSC32_OUT-Pad4)") (class "Default")
      (node (ref "U1") (pin "4") (pinfunction "PC15-OSC32_OUT_4") (pintype "bidirectional"))
    )
    (net (code "74") (name "unconnected-(U1-PD2-Pad54)") (class "Default")
      (node (ref "U1") (pin "54") (pinfunction "PD2_54") (pintype "bidirectional"))
    )
    (net (code "75") (name "unconnected-(U2-n.c.-Pad5)") (class "Default")
      (node (ref "U2") (pin "5") (pinfunction "n.c._5") (pintype "passive"))
    )
  )
)
